# SAML21_Xplained_Pro_current_measurement_.net
KiCad netlist of a schematic drawn in Altium Designer
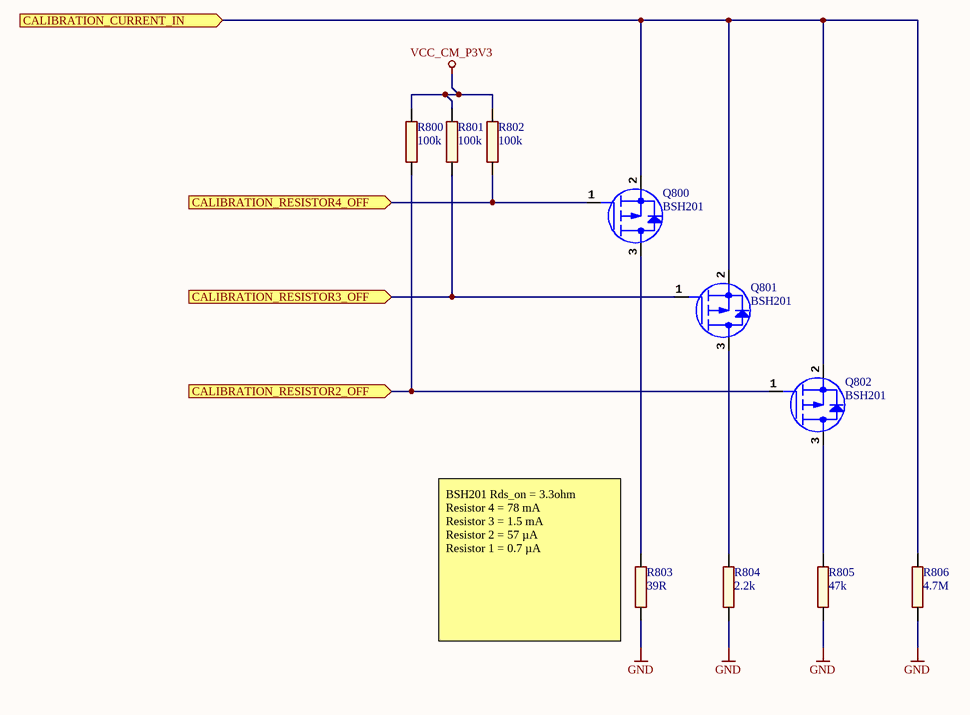
[diagram p0: SAML21_Xplained_Pro_current_measurement_calibration.SchDoc]

(export (version "E")
  (design (tool "Eeschema 10.0.6"))
  (components
    (comp (ref "Q800")
      (value "BSH201")
      (footprint "AP5-00002")
      (fields
        (field (name "MANUFACTURER") "NXP")
        (field (name "MPN") "BSH201,215")
        (field (name "Comment") "MOSFET_P_GSD")
      )
      (libsource (lib "AltiumDbLib") (part "MOSFET_P_GSD"))
    )
    (comp (ref "Q801")
      (value "BSH201")
      (footprint "AP5-00002")
      (fields
        (field (name "MANUFACTURER") "NXP")
        (field (name "MPN") "BSH201,215")
        (field (name "Comment") "MOSFET_P_GSD")
      )
      (libsource (lib "AltiumDbLib") (part "MOSFET_P_GSD"))
    )
    (comp (ref "Q802")
      (value "BSH201")
      (footprint "AP5-00002")
      (fields
        (field (name "MANUFACTURER") "NXP")
        (field (name "MPN") "BSH201,215")
        (field (name "Comment") "MOSFET_P_GSD")
      )
      (libsource (lib "AltiumDbLib") (part "MOSFET_P_GSD"))
    )
    (comp (ref "R800")
      (value "100k")
      (footprint "AP2-00011")
      (description "Thick film resistor, SMD 0402, 1/16W, 1%")
      (fields (field (name "TOLERANCE") "1 %") (field (name "Comment") "R2"))
      (libsource (lib "AltiumDbLib") (part "R2"))
    )
    (comp (ref "R801")
      (value "100k")
      (footprint "AP2-00011")
      (description "Thick film resistor, SMD 0402, 1/16W, 1%")
      (fields (field (name "TOLERANCE") "1 %") (field (name "Comment") "R2"))
      (libsource (lib "AltiumDbLib") (part "R2"))
    )
    (comp (ref "R802")
      (value "100k")
      (footprint "AP2-00011")
      (description "Thick film resistor, SMD 0402, 1/16W, 1%")
      (fields (field (name "TOLERANCE") "1 %") (field (name "Comment") "R2"))
      (libsource (lib "AltiumDbLib") (part "R2"))
    )
    (comp (ref "R803")
      (value "39R")
      (footprint "AP2-00011")
      (description "Thick film resistor, SMD 0402, 1/16W, 1%")
      (fields (field (name "TOLERANCE") "1 %") (field (name "Comment") "R2"))
      (libsource (lib "AltiumDbLib") (part "R2"))
    )
    (comp (ref "R804")
      (value "2.2k")
      (footprint "AP2-00011")
      (description "Thick film resistor, SMD 0402, 1/16W, 1%")
      (fields (field (name "TOLERANCE") "1 %") (field (name "Comment") "R2"))
      (libsource (lib "AltiumDbLib") (part "R2"))
    )
    (comp (ref "R805")
      (value "47k")
      (footprint "AP2-00011")
      (description "Thick film resistor, SMD 0402, 1/16W, 1%")
      (fields (field (name "TOLERANCE") "1 %") (field (name "Comment") "R2"))
      (libsource (lib "AltiumDbLib") (part "R2"))
    )
    (comp (ref "R806")
      (value "4.7M")
      (footprint "AP2-00011")
      (description "Thick film SMD 0402 1/16W 1%")
      (fields (field (name "TOLERANCE") "1 %") (field (name "Comment") "R2"))
      (libsource (lib "AltiumDbLib") (part "R2"))
    )
  )
  (nets
    (net (code "1") (name "/CALIBRATION_CURRENT_IN") (class "Default")
      (node (ref "Q800") (pin "2") (pinfunction "S_2") (pintype "passive"))
      (node (ref "Q801") (pin "2") (pinfunction "S_2") (pintype "passive"))
      (node (ref "Q802") (pin "2") (pinfunction "S_2") (pintype "passive"))
      (node (ref "R806") (pin "2") (pinfunction "2_2") (pintype "passive"))
    )
    (net (code "2") (name "/CALIBRATION_RESISTOR2_OFF") (class "Default")
      (node (ref "Q802") (pin "1") (pinfunction "G_1") (pintype "passive"))
      (node (ref "R800") (pin "1") (pinfunction "1_1") (pintype "passive"))
    )
    (net (code "3") (name "/CALIBRATION_RESISTOR3_OFF") (class "Default")
      (node (ref "Q801") (pin "1") (pinfunction "G_1") (pintype "passive"))
      (node (ref "R801") (pin "1") (pinfunction "1_1") (pintype "passive"))
    )
    (net (code "4") (name "/CALIBRATION_RESISTOR4_OFF") (class "Default")
      (node (ref "Q800") (pin "1") (pinfunction "G_1") (pintype "passive"))
      (node (ref "R802") (pin "1") (pinfunction "1_1") (pintype "passive"))
    )
    (net (code "5") (name "GND") (class "Default")
      (node (ref "R803") (pin "1") (pinfunction "1_1") (pintype "passive"))
      (node (ref "R804") (pin "1") (pinfunction "1_1") (pintype "passive"))
      (node (ref "R805") (pin "1") (pinfunction "1_1") (pintype "passive"))
      (node (ref "R806") (pin "1") (pinfunction "1_1") (pintype "passive"))
    )
    (net (code "6") (name "Net-(Q800-D)") (class "Default")
      (node (ref "Q800") (pin "3") (pinfunction "D_3") (pintype "passive"))
      (node (ref "R803") (pin "2") (pinfunction "2_2") (pintype "passive"))
    )
    (net (code "7") (name "Net-(Q801-D)") (class "Default")
      (node (ref "Q801") (pin "3") (pinfunction "D_3") (pintype "passive"))
      (node (ref "R804") (pin "2") (pinfunction "2_2") (pintype "passive"))
    )
    (net (code "8") (name "Net-(Q802-D)") (class "Default")
      (node (ref "Q802") (pin "3") (pinfunction "D_3") (pintype "passive"))
      (node (ref "R805") (pin "2") (pinfunction "2_2") (pintype "passive"))
    )
    (net (code "9") (name "VCC_CM_P3V3") (class "Default")
      (node (ref "R800") (pin "2") (pinfunction "2_2") (pintype "passive"))
      (node (ref "R801") (pin "2") (pinfunction "2_2") (pintype "passive"))
      (node (ref "R802") (pin "2") (pinfunction "2_2") (pintype "passive"))
    )
  )
)
